# My__V5.net
KiCad netlist of a schematic drawn in Altium Designer
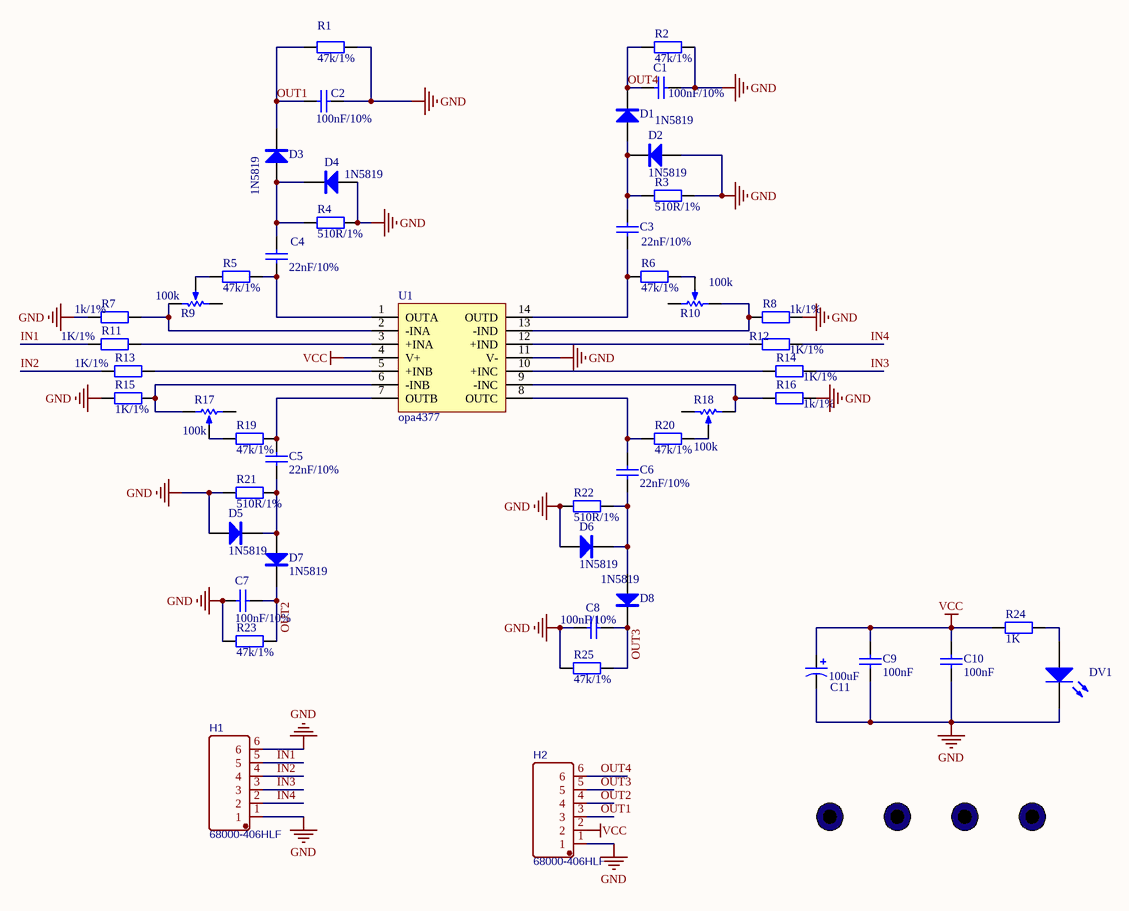
[diagram p0: My电磁_V5.SchDoc]

(export (version "E")
  (design (tool "Eeschema 10.0.6"))
  (components
    (comp (ref "C1")
      (value "100nF/10%")
      (footprint "C 0805_L")
      (description "Capacitor")
      (libsource (lib "PCB_Project") (part "Cap"))
    )
    (comp (ref "C2")
      (value "100nF/10%")
      (footprint "C 0805_L")
      (description "Capacitor")
      (libsource (lib "PCB_Project") (part "Cap"))
    )
    (comp (ref "C3")
      (value "22nF/10%")
      (footprint "C 0805_L")
      (description "Capacitor")
      (libsource (lib "PCB_Project") (part "Cap"))
    )
    (comp (ref "C4")
      (value "22nF/10%")
      (footprint "C 0805_L")
      (description "Capacitor")
      (libsource (lib "PCB_Project") (part "Cap"))
    )
    (comp (ref "C5")
      (value "22nF/10%")
      (footprint "C 0805_L")
      (description "Capacitor")
      (libsource (lib "PCB_Project") (part "Cap"))
    )
    (comp (ref "C6")
      (value "22nF/10%")
      (footprint "C 0805_L")
      (description "Capacitor")
      (libsource (lib "PCB_Project") (part "Cap"))
    )
    (comp (ref "C7")
      (value "100nF/10%")
      (footprint "C 0805_L")
      (description "Capacitor")
      (libsource (lib "PCB_Project") (part "Cap"))
    )
    (comp (ref "C8")
      (value "100nF/10%")
      (footprint "C 0805_L")
      (description "Capacitor")
      (libsource (lib "PCB_Project") (part "Cap"))
    )
    (comp (ref "C9")
      (value "100nF")
      (footprint "C 0805_L")
      (description "Capacitor")
      (libsource (lib "PCB_Project") (part "Cap"))
    )
    (comp (ref "C10")
      (value "100nF")
      (footprint "C 0805_L")
      (description "Capacitor")
      (libsource (lib "PCB_Project") (part "Cap"))
    )
    (comp (ref "C11")
      (value "100uF")
      (footprint "CD A(3216)")
      (libsource (lib "PCB_Project") (part "CAP-AUX"))
    )
    (comp (ref "D1")
      (value "1N5819")
      (footprint "SOD-323")
      (description "肖特基二极管")
      (fields (field (name "版权归属") "源创客"))
      (libsource (lib "PCB_Project") (part "1N5819"))
    )
    (comp (ref "D2")
      (value "1N5819")
      (footprint "SOD-323")
      (description "肖特基二极管")
      (fields (field (name "版权归属") "源创客"))
      (libsource (lib "PCB_Project") (part "1N5819"))
    )
    (comp (ref "D3")
      (value "1N5819")
      (footprint "SOD-323")
      (description "肖特基二极管")
      (fields (field (name "版权归属") "源创客"))
      (libsource (lib "PCB_Project") (part "1N5819"))
    )
    (comp (ref "D4")
      (value "1N5819")
      (footprint "SOD-323")
      (description "肖特基二极管")
      (fields (field (name "版权归属") "源创客"))
      (libsource (lib "PCB_Project") (part "1N5819"))
    )
    (comp (ref "D5")
      (value "1N5819")
      (footprint "SOD-323")
      (description "肖特基二极管")
      (fields (field (name "版权归属") "源创客"))
      (libsource (lib "PCB_Project") (part "1N5819"))
    )
    (comp (ref "D6")
      (value "1N5819")
      (footprint "SOD-323")
      (description "肖特基二极管")
      (fields (field (name "版权归属") "源创客"))
      (libsource (lib "PCB_Project") (part "1N5819"))
    )
    (comp (ref "D7")
      (value "1N5819")
      (footprint "SOD-323")
      (description "肖特基二极管")
      (fields (field (name "版权归属") "源创客"))
      (libsource (lib "PCB_Project") (part "1N5819"))
    )
    (comp (ref "D8")
      (value "1N5819")
      (footprint "SOD-323")
      (description "肖特基二极管")
      (fields (field (name "版权归属") "源创客"))
      (libsource (lib "PCB_Project") (part "1N5819"))
    )
    (comp (ref "DV1")
      (value "Red-0603")
      (footprint "LQ_LED0603R")
      (description "Typical RED, GREEN, YELLOW, AMBER GaAs LED")
      (fields (field (name "PUBLISHER") "Altium Limited"))
      (libsource (lib "LQ4377M8CHV1") (part "LED2"))
    )
    (comp (ref "H1")
      (value "68000-406HLF")
      (footprint "6p1:HDR-TH_6P-P2.54-V")
      (fields (field (name "BOM_SUPPLIER PART") "C178289") (field (name "CONTRIBUTOR") "LCSC"))
      (libsource (lib "6p") (part "68000-406HLF"))
    )
    (comp (ref "H2")
      (value "68000-406HLF")
      (footprint "6p1:HDR-TH_6P-P2.54-V")
      (fields (field (name "BOM_SUPPLIER PART") "C178289") (field (name "CONTRIBUTOR") "LCSC"))
      (libsource (lib "6p") (part "68000-406HLF"))
    )
    (comp (ref "R1")
      (value "47k/1%")
      (footprint "R 0805_L")
      (description "Resistor")
      (fields (field (name "Comment") "Res2") (field (name "PUBLISHER") "Altium Limited"))
      (libsource (lib "") (part "R 0805_1"))
    )
    (comp (ref "R2")
      (value "47k/1%")
      (footprint "R 0805_L")
      (description "Resistor")
      (fields (field (name "Comment") "Res2") (field (name "PUBLISHER") "Altium Limited"))
      (libsource (lib "") (part "R 0805_2"))
    )
    (comp (ref "R3")
      (value "510R/1%")
      (footprint "R 0805_L")
      (description "Resistor")
      (fields (field (name "Comment") "Res2") (field (name "PUBLISHER") "Altium Limited"))
      (libsource (lib "") (part "R 0805_2"))
    )
    (comp (ref "R4")
      (value "510R/1%")
      (footprint "R 0805_L")
      (description "Resistor")
      (fields (field (name "Comment") "Res2") (field (name "PUBLISHER") "Altium Limited"))
      (libsource (lib "") (part "R 0805_1"))
    )
    (comp (ref "R5")
      (value "47k/1%")
      (footprint "R 0805_L")
      (description "Resistor")
      (fields (field (name "Comment") "Res2") (field (name "PUBLISHER") "Altium Limited"))
      (libsource (lib "PCB_Project") (part "R 0805"))
    )
    (comp (ref "R6")
      (value "47k/1%")
      (footprint "R 0805_L")
      (description "Resistor")
      (fields (field (name "Comment") "Res2") (field (name "PUBLISHER") "Altium Limited"))
      (libsource (lib "") (part "R 0805_2"))
    )
    (comp (ref "R7")
      (value "1k/1%")
      (footprint "R 0805_L")
      (description "Resistor")
      (fields (field (name "Comment") "Res2") (field (name "PUBLISHER") "Altium Limited"))
      (libsource (lib "PCB_Project") (part "R 0805"))
    )
    (comp (ref "R8")
      (value "1k/1%")
      (footprint "R 0805_L")
      (description "Resistor")
      (fields (field (name "Comment") "Res2") (field (name "PUBLISHER") "Altium Limited"))
      (libsource (lib "") (part "R 0805_2"))
    )
    (comp (ref "R9")
      (value "100k")
      (footprint "电位计")
      (description "节电实验室")
      (libsource (lib "GHL_K60_100P") (part "电位器"))
    )
    (comp (ref "R10")
      (value "100k")
      (footprint "电位计")
      (description "节电实验室")
      (libsource (lib "GHL_K60_100P") (part "电位器"))
    )
    (comp (ref "R11")
      (value "1K/1%")
      (footprint "R 0805_L")
      (description "Resistor")
      (fields (field (name "Comment") "Res2") (field (name "PUBLISHER") "Altium Limited"))
      (libsource (lib "PCB_Project") (part "R 0805"))
    )
    (comp (ref "R12")
      (value "1K/1%")
      (footprint "R 0805_L")
      (description "Resistor")
      (fields (field (name "Comment") "Res2") (field (name "PUBLISHER") "Altium Limited"))
      (libsource (lib "") (part "R 0805_2"))
    )
    (comp (ref "R13")
      (value "1K/1%")
      (footprint "R 0805_L")
      (description "Resistor")
      (fields (field (name "Comment") "Res2") (field (name "PUBLISHER") "Altium Limited"))
      (libsource (lib "") (part "R 0805_1"))
    )
    (comp (ref "R14")
      (value "1K/1%")
      (footprint "R 0805_L")
      (description "Resistor")
      (fields (field (name "Comment") "Res2") (field (name "PUBLISHER") "Altium Limited"))
      (libsource (lib "") (part "R 0805_3"))
    )
    (comp (ref "R15")
      (value "1K/1%")
      (footprint "R 0805_L")
      (description "Resistor")
      (fields (field (name "Comment") "Res2") (field (name "PUBLISHER") "Altium Limited"))
      (libsource (lib "") (part "R 0805_1"))
    )
    (comp (ref "R16")
      (value "1k/1%")
      (footprint "R 0805_L")
      (description "Resistor")
      (fields (field (name "Comment") "Res2") (field (name "PUBLISHER") "Altium Limited"))
      (libsource (lib "") (part "R 0805_3"))
    )
    (comp (ref "R17")
      (value "100k")
      (footprint "电位计")
      (description "节电实验室")
      (libsource (lib "GHL_K60_100P") (part "电位器"))
    )
    (comp (ref "R18")
      (value "100k")
      (footprint "电位计")
      (description "节电实验室")
      (libsource (lib "GHL_K60_100P") (part "电位器"))
    )
    (comp (ref "R19")
      (value "47k/1%")
      (footprint "R 0805_L")
      (description "Resistor")
      (fields (field (name "Comment") "Res2") (field (name "PUBLISHER") "Altium Limited"))
      (libsource (lib "") (part "R 0805_1"))
    )
    (comp (ref "R20")
      (value "47k/1%")
      (footprint "R 0805_L")
      (description "Resistor")
      (fields (field (name "Comment") "Res2") (field (name "PUBLISHER") "Altium Limited"))
      (libsource (lib "") (part "R 0805_3"))
    )
    (comp (ref "R21")
      (value "510R/1%")
      (footprint "R 0805_L")
      (description "Resistor")
      (fields (field (name "Comment") "Res2") (field (name "PUBLISHER") "Altium Limited"))
      (libsource (lib "") (part "R 0805_1"))
    )
    (comp (ref "R22")
      (value "510R/1%")
      (footprint "R 0805_L")
      (description "Resistor")
      (fields (field (name "Comment") "Res2") (field (name "PUBLISHER") "Altium Limited"))
      (libsource (lib "") (part "R 0805_1"))
    )
    (comp (ref "R23")
      (value "47k/1%")
      (footprint "R 0805_L")
      (description "Resistor")
      (fields (field (name "Comment") "Res2") (field (name "PUBLISHER") "Altium Limited"))
      (libsource (lib "") (part "R 0805_1"))
    )
    (comp (ref "R24")
      (value "1K")
      (footprint "R 0805_L")
      (description "Resistor")
      (fields (field (name "Comment") "Res2") (field (name "PUBLISHER") "Altium Limited"))
      (libsource (lib "") (part "R 0805_1"))
    )
    (comp (ref "R25")
      (value "47k/1%")
      (footprint "R 0805_L")
      (description "Resistor")
      (fields (field (name "Comment") "Res2") (field (name "PUBLISHER") "Altium Limited"))
      (libsource (lib "") (part "R 0805_1"))
    )
    (comp (ref "SCROW1")
      (value "SCROW")
      (footprint "LQ_SCROW3&5mm")
      (description "Connector")
      (libsource (lib "LQ4377M8CHV1") (part "SCROW"))
    )
    (comp (ref "SCROW2")
      (value "SCROW")
      (footprint "LQ_SCROW3&5mm")
      (description "Connector")
      (libsource (lib "LQ4377M8CHV1") (part "SCROW"))
    )
    (comp (ref "SCROW3")
      (value "SCROW")
      (footprint "LQ_SCROW3&5mm")
      (description "Connector")
      (libsource (lib "LQ4377M8CHV1") (part "SCROW"))
    )
    (comp (ref "SCROW4")
      (value "SCROW")
      (footprint "LQ_SCROW3&5mm")
      (description "Connector")
      (libsource (lib "LQ4377M8CHV1") (part "SCROW"))
    )
    (comp (ref "U1")
      (value "opa4377")
      (footprint "TSSOP-14")
      (libsource (lib "PCB_Project") (part "opa4377"))
    )
  )
  (nets
    (net (code "2") (name "/IN1") (class "Default")
      (node (ref "H1") (pin "5") (pinfunction "5_5") (pintype "passive"))
      (node (ref "R11") (pin "2") (pinfunction "2_2") (pintype "passive"))
    )
    (net (code "3") (name "/IN2") (class "Default")
      (node (ref "H1") (pin "4") (pinfunction "4_4") (pintype "passive"))
      (node (ref "R13") (pin "2") (pinfunction "2_2") (pintype "passive"))
    )
    (net (code "4") (name "/IN3") (class "Default")
      (node (ref "H1") (pin "3") (pinfunction "3_3") (pintype "passive"))
      (node (ref "R14") (pin "2") (pinfunction "2_2") (pintype "passive"))
    )
    (net (code "5") (name "/IN4") (class "Default")
      (node (ref "H1") (pin "2") (pinfunction "2_2") (pintype "passive"))
      (node (ref "R12") (pin "2") (pinfunction "2_2") (pintype "passive"))
    )
    (net (code "6") (name "/OUT1") (class "Default")
      (node (ref "C2") (pin "2") (pinfunction "2_2") (pintype "passive"))
      (node (ref "D3") (pin "2") (pinfunction "K_2") (pintype "passive"))
      (node (ref "H2") (pin "3") (pinfunction "3_3") (pintype "passive"))
      (node (ref "R1") (pin "2") (pinfunction "2_2") (pintype "passive"))
    )
    (net (code "7") (name "/OUT2") (class "Default")
      (node (ref "C7") (pin "2") (pinfunction "2_2") (pintype "passive"))
      (node (ref "D7") (pin "2") (pinfunction "K_2") (pintype "passive"))
      (node (ref "H2") (pin "4") (pinfunction "4_4") (pintype "passive"))
      (node (ref "R23") (pin "1") (pinfunction "1_1") (pintype "passive"))
    )
    (net (code "8") (name "/OUT3") (class "Default")
      (node (ref "C8") (pin "2") (pinfunction "2_2") (pintype "passive"))
      (node (ref "D8") (pin "2") (pinfunction "K_2") (pintype "passive"))
      (node (ref "H2") (pin "5") (pinfunction "5_5") (pintype "passive"))
      (node (ref "R25") (pin "1") (pinfunction "1_1") (pintype "passive"))
    )
    (net (code "9") (name "/OUT4") (class "Default")
      (node (ref "C1") (pin "1") (pinfunction "1_1") (pintype "passive"))
      (node (ref "D1") (pin "2") (pinfunction "K_2") (pintype "passive"))
      (node (ref "H2") (pin "6") (pinfunction "6_6") (pintype "passive"))
      (node (ref "R2") (pin "1") (pinfunction "1_1") (pintype "passive"))
    )
    (net (code "10") (name "GND") (class "Default")
      (node (ref "C1") (pin "2") (pinfunction "2_2") (pintype "passive"))
      (node (ref "C10") (pin "1") (pinfunction "1_1") (pintype "passive"))
      (node (ref "C11") (pin "2") (pinfunction "2_2") (pintype "passive"))
      (node (ref "C2") (pin "1") (pinfunction "1_1") (pintype "passive"))
      (node (ref "C7") (pin "1") (pinfunction "1_1") (pintype "passive"))
      (node (ref "C8") (pin "1") (pinfunction "1_1") (pintype "passive"))
      (node (ref "C9") (pin "1") (pinfunction "1_1") (pintype "passive"))
      (node (ref "D2") (pin "1") (pinfunction "A_1") (pintype "passive"))
      (node (ref "D4") (pin "1") (pinfunction "A_1") (pintype "passive"))
      (node (ref "D5") (pin "1") (pinfunction "A_1") (pintype "passive"))
      (node (ref "D6") (pin "1") (pinfunction "A_1") (pintype "passive"))
      (node (ref "DV1") (pin "2") (pinfunction "K_2") (pintype "passive"))
      (node (ref "H1") (pin "1") (pinfunction "1_1") (pintype "passive"))
      (node (ref "H1") (pin "6") (pinfunction "6_6") (pintype "passive"))
      (node (ref "H2") (pin "1") (pinfunction "1_1") (pintype "passive"))
      (node (ref "R1") (pin "1") (pinfunction "1_1") (pintype "passive"))
      (node (ref "R15") (pin "2") (pinfunction "2_2") (pintype "passive"))
      (node (ref "R16") (pin "2") (pinfunction "2_2") (pintype "passive"))
      (node (ref "R2") (pin "2") (pinfunction "2_2") (pintype "passive"))
      (node (ref "R21") (pin "2") (pinfunction "2_2") (pintype "passive"))
      (node (ref "R22") (pin "2") (pinfunction "2_2") (pintype "passive"))
      (node (ref "R23") (pin "2") (pinfunction "2_2") (pintype "passive"))
      (node (ref "R25") (pin "2") (pinfunction "2_2") (pintype "passive"))
      (node (ref "R3") (pin "2") (pinfunction "2_2") (pintype "passive"))
      (node (ref "R4") (pin "1") (pinfunction "1_1") (pintype "passive"))
      (node (ref "R7") (pin "2") (pinfunction "2_2") (pintype "passive"))
      (node (ref "R8") (pin "2") (pinfunction "2_2") (pintype "passive"))
      (node (ref "U1") (pin "11") (pinfunction "V-_11") (pintype "passive"))
    )
    (net (code "11") (name "Net-(D1-A)") (class "Default")
      (node (ref "C3") (pin "2") (pinfunction "2_2") (pintype "passive"))
      (node (ref "D1") (pin "1") (pinfunction "A_1") (pintype "passive"))
      (node (ref "D2") (pin "2") (pinfunction "K_2") (pintype "passive"))
      (node (ref "R3") (pin "1") (pinfunction "1_1") (pintype "passive"))
    )
    (net (code "12") (name "Net-(D3-A)") (class "Default")
      (node (ref "C4") (pin "2") (pinfunction "2_2") (pintype "passive"))
      (node (ref "D3") (pin "1") (pinfunction "A_1") (pintype "passive"))
      (node (ref "D4") (pin "2") (pinfunction "K_2") (pintype "passive"))
      (node (ref "R4") (pin "2") (pinfunction "2_2") (pintype "passive"))
    )
    (net (code "13") (name "Net-(D5-K)") (class "Default")
      (node (ref "C5") (pin "1") (pinfunction "1_1") (pintype "passive"))
      (node (ref "D5") (pin "2") (pinfunction "K_2") (pintype "passive"))
      (node (ref "D7") (pin "1") (pinfunction "A_1") (pintype "passive"))
      (node (ref "R21") (pin "1") (pinfunction "1_1") (pintype "passive"))
    )
    (net (code "14") (name "Net-(D6-K)") (class "Default")
      (node (ref "C6") (pin "1") (pinfunction "1_1") (pintype "passive"))
      (node (ref "D6") (pin "2") (pinfunction "K_2") (pintype "passive"))
      (node (ref "D8") (pin "1") (pinfunction "A_1") (pintype "passive"))
      (node (ref "R22") (pin "1") (pinfunction "1_1") (pintype "passive"))
    )
    (net (code "15") (name "Net-(DV1-A)") (class "Default")
      (node (ref "DV1") (pin "1") (pinfunction "A_1") (pintype "passive"))
      (node (ref "R24") (pin "1") (pinfunction "1_1") (pintype "passive"))
    )
    (net (code "16") (name "Net-(R9-TAP)") (class "Default")
      (node (ref "R5") (pin "2") (pinfunction "2_2") (pintype "passive"))
      (node (ref "R9") (pin "2") (pinfunction "TAP_2") (pintype "passive"))
    )
    (net (code "17") (name "Net-(R9-TOP)") (class "Default")
      (node (ref "R7") (pin "1") (pinfunction "1_1") (pintype "passive"))
      (node (ref "R9") (pin "3") (pinfunction "TOP_3") (pintype "passive"))
      (node (ref "U1") (pin "2") (pinfunction "-INA_2") (pintype "passive"))
    )
    (net (code "18") (name "Net-(R10-TAP)") (class "Default")
      (node (ref "R10") (pin "2") (pinfunction "TAP_2") (pintype "passive"))
      (node (ref "R6") (pin "2") (pinfunction "2_2") (pintype "passive"))
    )
    (net (code "19") (name "Net-(R10-TOP)") (class "Default")
      (node (ref "R10") (pin "3") (pinfunction "TOP_3") (pintype "passive"))
      (node (ref "R8") (pin "1") (pinfunction "1_1") (pintype "passive"))
      (node (ref "U1") (pin "13") (pinfunction "-IND_13") (pintype "passive"))
    )
    (net (code "20") (name "Net-(R17-TAP)") (class "Default")
      (node (ref "R17") (pin "2") (pinfunction "TAP_2") (pintype "passive"))
      (node (ref "R19") (pin "2") (pinfunction "2_2") (pintype "passive"))
    )
    (net (code "21") (name "Net-(R17-TOP)") (class "Default")
      (node (ref "R15") (pin "1") (pinfunction "1_1") (pintype "passive"))
      (node (ref "R17") (pin "3") (pinfunction "TOP_3") (pintype "passive"))
      (node (ref "U1") (pin "6") (pinfunction "-INB_6") (pintype "passive"))
    )
    (net (code "22") (name "Net-(R18-TAP)") (class "Default")
      (node (ref "R18") (pin "2") (pinfunction "TAP_2") (pintype "passive"))
      (node (ref "R20") (pin "2") (pinfunction "2_2") (pintype "passive"))
    )
    (net (code "23") (name "Net-(R18-TOP)") (class "Default")
      (node (ref "R16") (pin "1") (pinfunction "1_1") (pintype "passive"))
      (node (ref "R18") (pin "3") (pinfunction "TOP_3") (pintype "passive"))
      (node (ref "U1") (pin "9") (pinfunction "-INC_9") (pintype "passive"))
    )
    (net (code "24") (name "Net-(U1-+INA)") (class "Default")
      (node (ref "R11") (pin "1") (pinfunction "1_1") (pintype "passive"))
      (node (ref "U1") (pin "3") (pinfunction "+INA_3") (pintype "passive"))
    )
    (net (code "25") (name "Net-(U1-+INB)") (class "Default")
      (node (ref "R13") (pin "1") (pinfunction "1_1") (pintype "passive"))
      (node (ref "U1") (pin "5") (pinfunction "+INB_5") (pintype "passive"))
    )
    (net (code "26") (name "Net-(U1-+INC)") (class "Default")
      (node (ref "R14") (pin "1") (pinfunction "1_1") (pintype "passive"))
      (node (ref "U1") (pin "10") (pinfunction "+INC_10") (pintype "passive"))
    )
    (net (code "27") (name "Net-(U1-+IND)") (class "Default")
      (node (ref "R12") (pin "1") (pinfunction "1_1") (pintype "passive"))
      (node (ref "U1") (pin "12") (pinfunction "+IND_12") (pintype "passive"))
    )
    (net (code "28") (name "Net-(U1-OUTA)") (class "Default")
      (node (ref "C4") (pin "1") (pinfunction "1_1") (pintype "passive"))
      (node (ref "R5") (pin "1") (pinfunction "1_1") (pintype "passive"))
      (node (ref "U1") (pin "1") (pinfunction "OUTA_1") (pintype "passive"))
    )
    (net (code "29") (name "Net-(U1-OUTB)") (class "Default")
      (node (ref "C5") (pin "2") (pinfunction "2_2") (pintype "passive"))
      (node (ref "R19") (pin "1") (pinfunction "1_1") (pintype "passive"))
      (node (ref "U1") (pin "7") (pinfunction "OUTB_7") (pintype "passive"))
    )
    (net (code "30") (name "Net-(U1-OUTC)") (class "Default")
      (node (ref "C6") (pin "2") (pinfunction "2_2") (pintype "passive"))
      (node (ref "R20") (pin "1") (pinfunction "1_1") (pintype "passive"))
      (node (ref "U1") (pin "8") (pinfunction "OUTC_8") (pintype "passive"))
    )
    (net (code "31") (name "Net-(U1-OUTD)") (class "Default")
      (node (ref "C3") (pin "1") (pinfunction "1_1") (pintype "passive"))
      (node (ref "R6") (pin "1") (pinfunction "1_1") (pintype "passive"))
      (node (ref "U1") (pin "14") (pinfunction "OUTD_14") (pintype "passive"))
    )
    (net (code "32") (name "VCC") (class "Default")
      (node (ref "C10") (pin "2") (pinfunction "2_2") (pintype "passive"))
      (node (ref "C11") (pin "1") (pinfunction "1_1") (pintype "passive"))
      (node (ref "C9") (pin "2") (pinfunction "2_2") (pintype "passive"))
      (node (ref "H2") (pin "2") (pinfunction "2_2") (pintype "passive"))
      (node (ref "R24") (pin "2") (pinfunction "2_2") (pintype "passive"))
      (node (ref "U1") (pin "4") (pinfunction "V+_4") (pintype "passive"))
    )
    (net (code "33") (name "unconnected-(R9-BOT-Pad1)") (class "Default")
      (node (ref "R9") (pin "1") (pinfunction "BOT_1") (pintype "passive"))
    )
    (net (code "34") (name "unconnected-(R10-BOT-Pad1)") (class "Default")
      (node (ref "R10") (pin "1") (pinfunction "BOT_1") (pintype "passive"))
    )
    (net (code "35") (name "unconnected-(R17-BOT-Pad1)") (class "Default")
      (node (ref "R17") (pin "1") (pinfunction "BOT_1") (pintype "passive"))
    )
    (net (code "36") (name "unconnected-(R18-BOT-Pad1)") (class "Default")
      (node (ref "R18") (pin "1") (pinfunction "BOT_1") (pintype "passive"))
    )
    (net (code "37") (name "unconnected-(SCROW1-Pad1)") (class "Default")
      (node (ref "SCROW1") (pin "1") (pinfunction "1_1") (pintype "passive"))
    )
    (net (code "38") (name "unconnected-(SCROW2-Pad1)") (class "Default")
      (node (ref "SCROW2") (pin "1") (pinfunction "1_1") (pintype "passive"))
    )
    (net (code "39") (name "unconnected-(SCROW3-Pad1)") (class "Default")
      (node (ref "SCROW3") (pin "1") (pinfunction "1_1") (pintype "passive"))
    )
    (net (code "40") (name "unconnected-(SCROW4-Pad1)") (class "Default")
      (node (ref "SCROW4") (pin "1") (pinfunction "1_1") (pintype "passive"))
    )
  )
)
